# charginator_v1.net
KiCad netlist of a schematic drawn in EAGLE
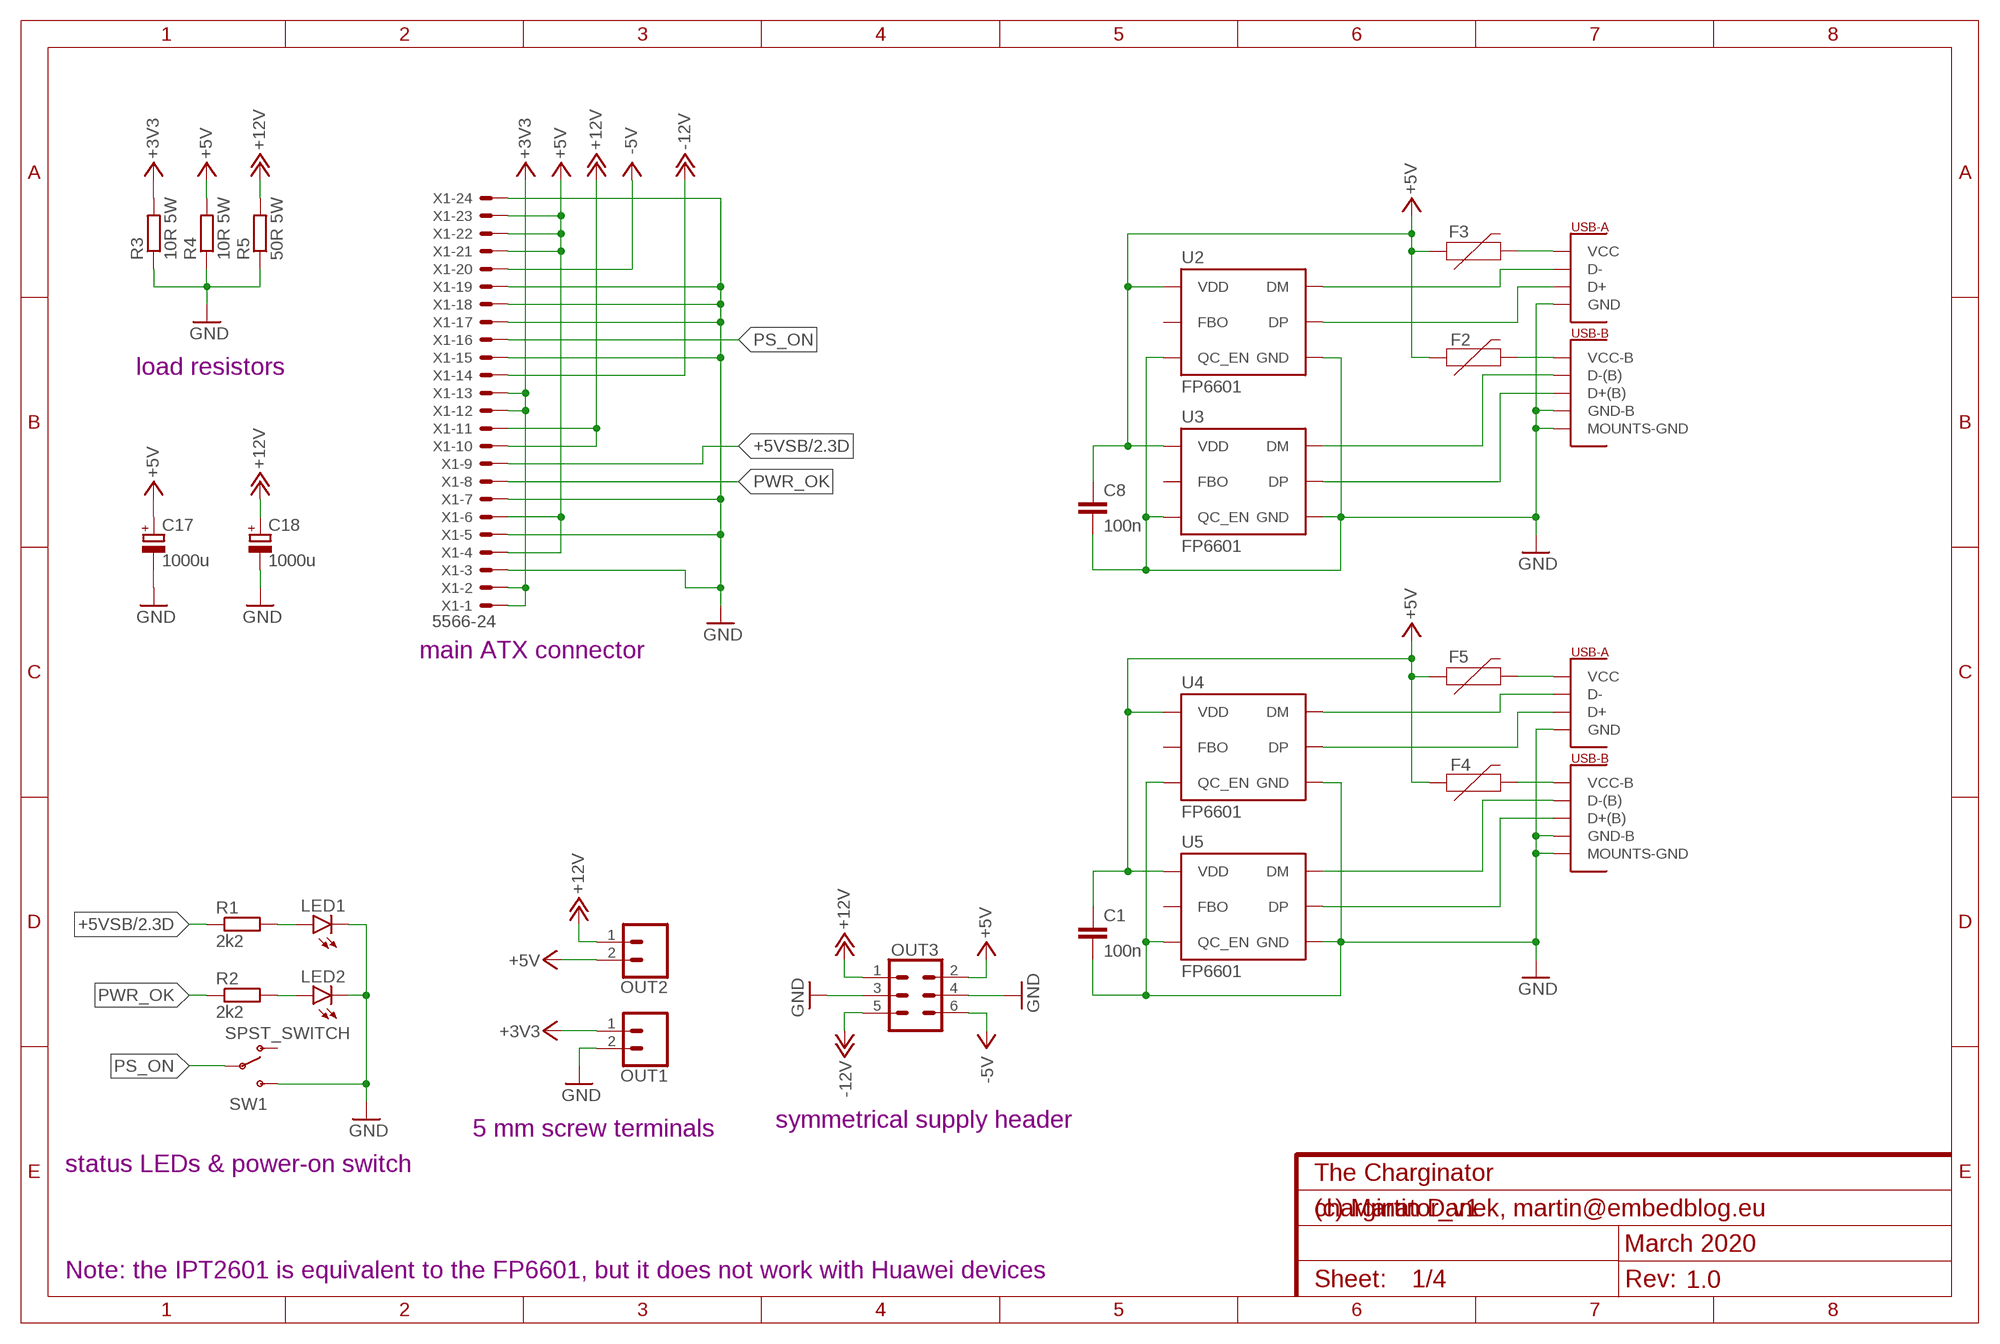
[diagram p0: schematic, sheet 1]
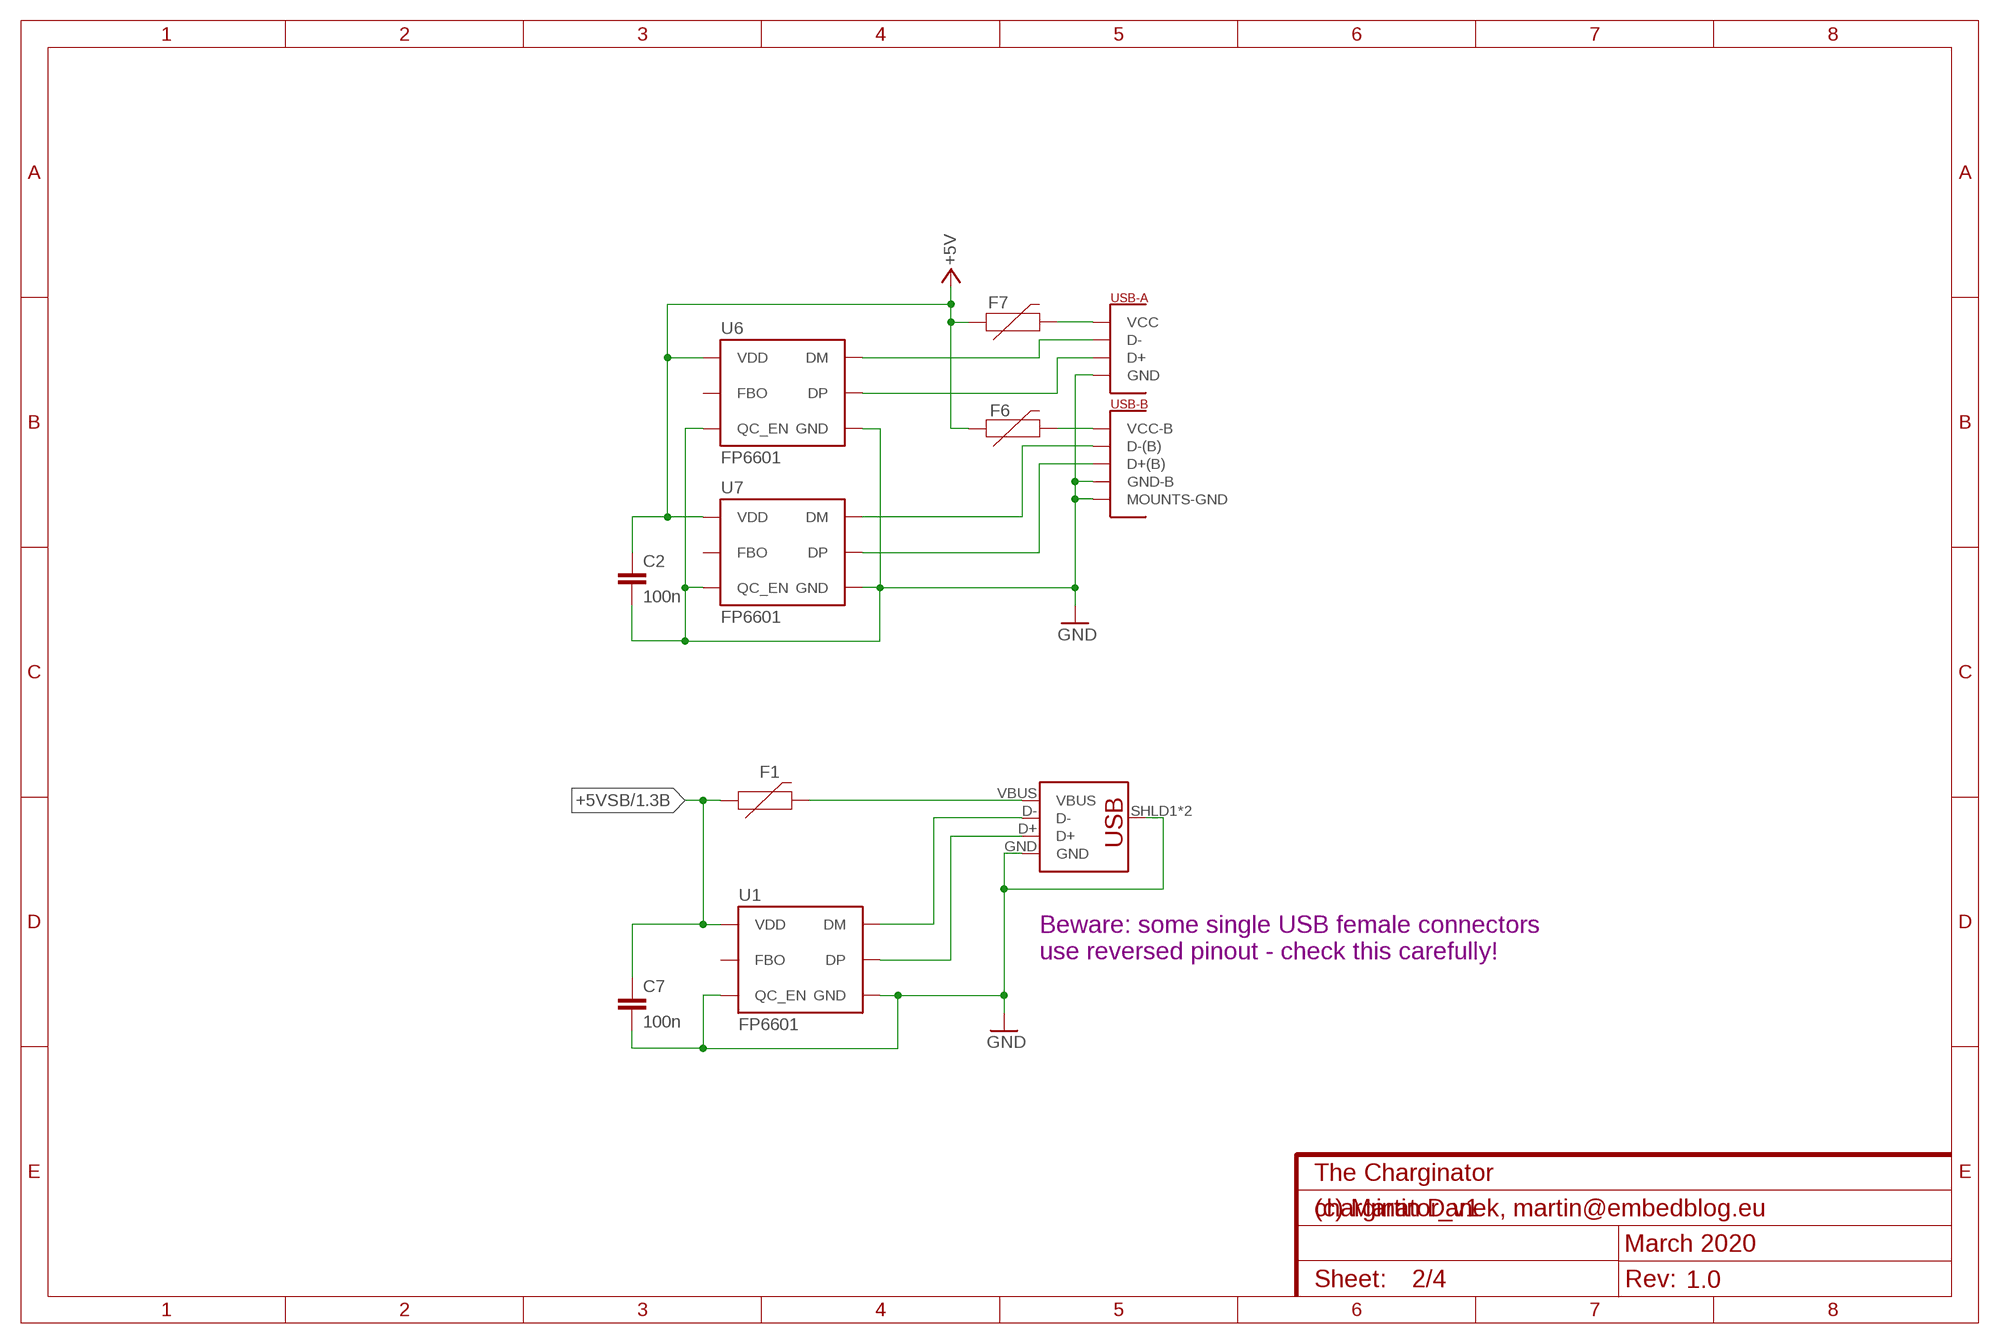
[diagram p1: schematic, sheet 2]
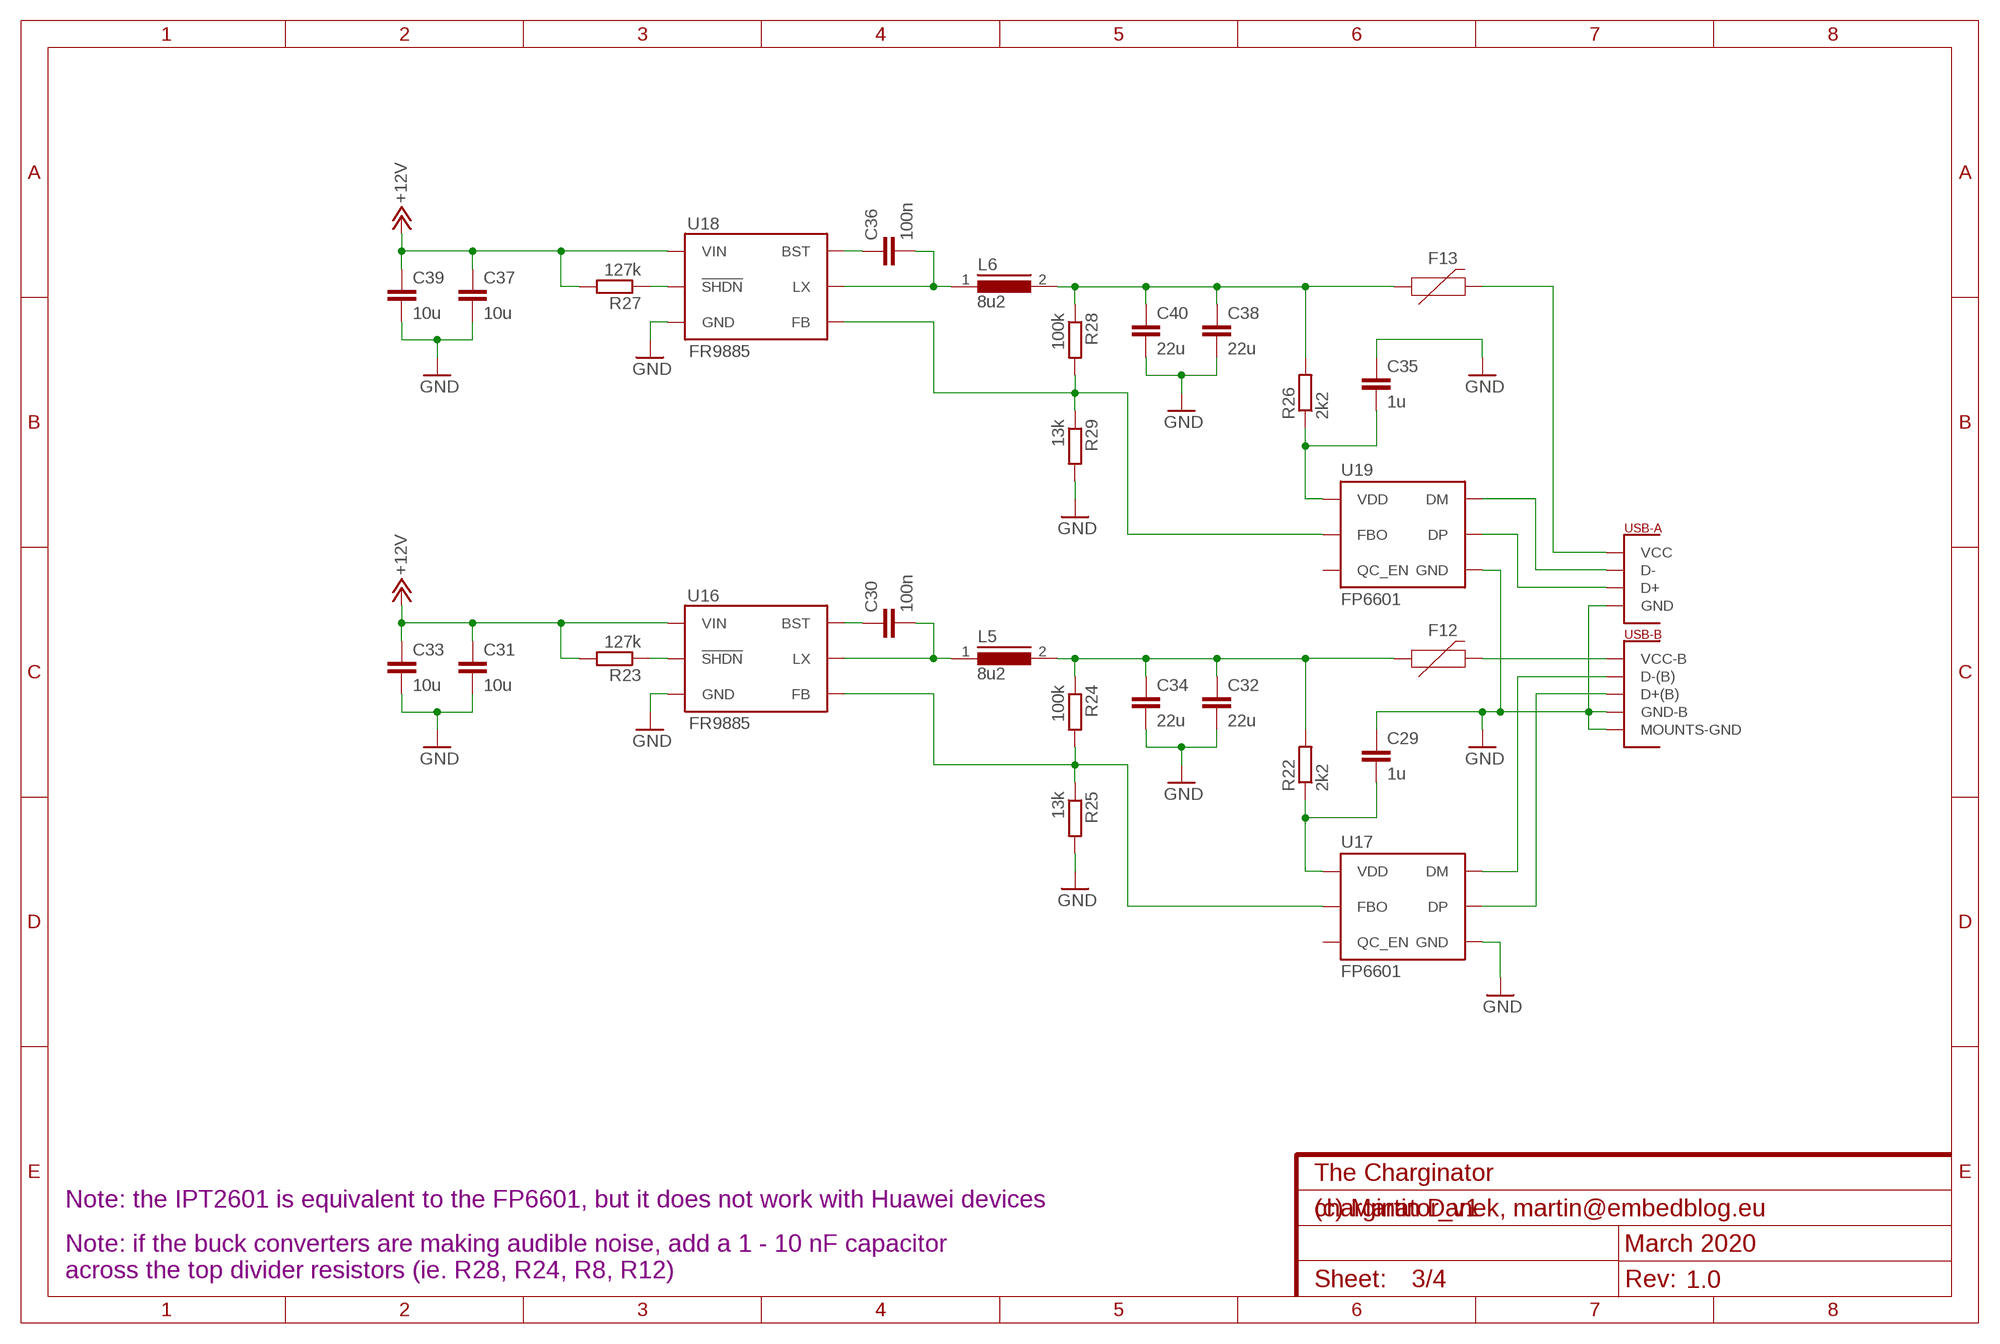
[diagram p2: schematic, sheet 3]
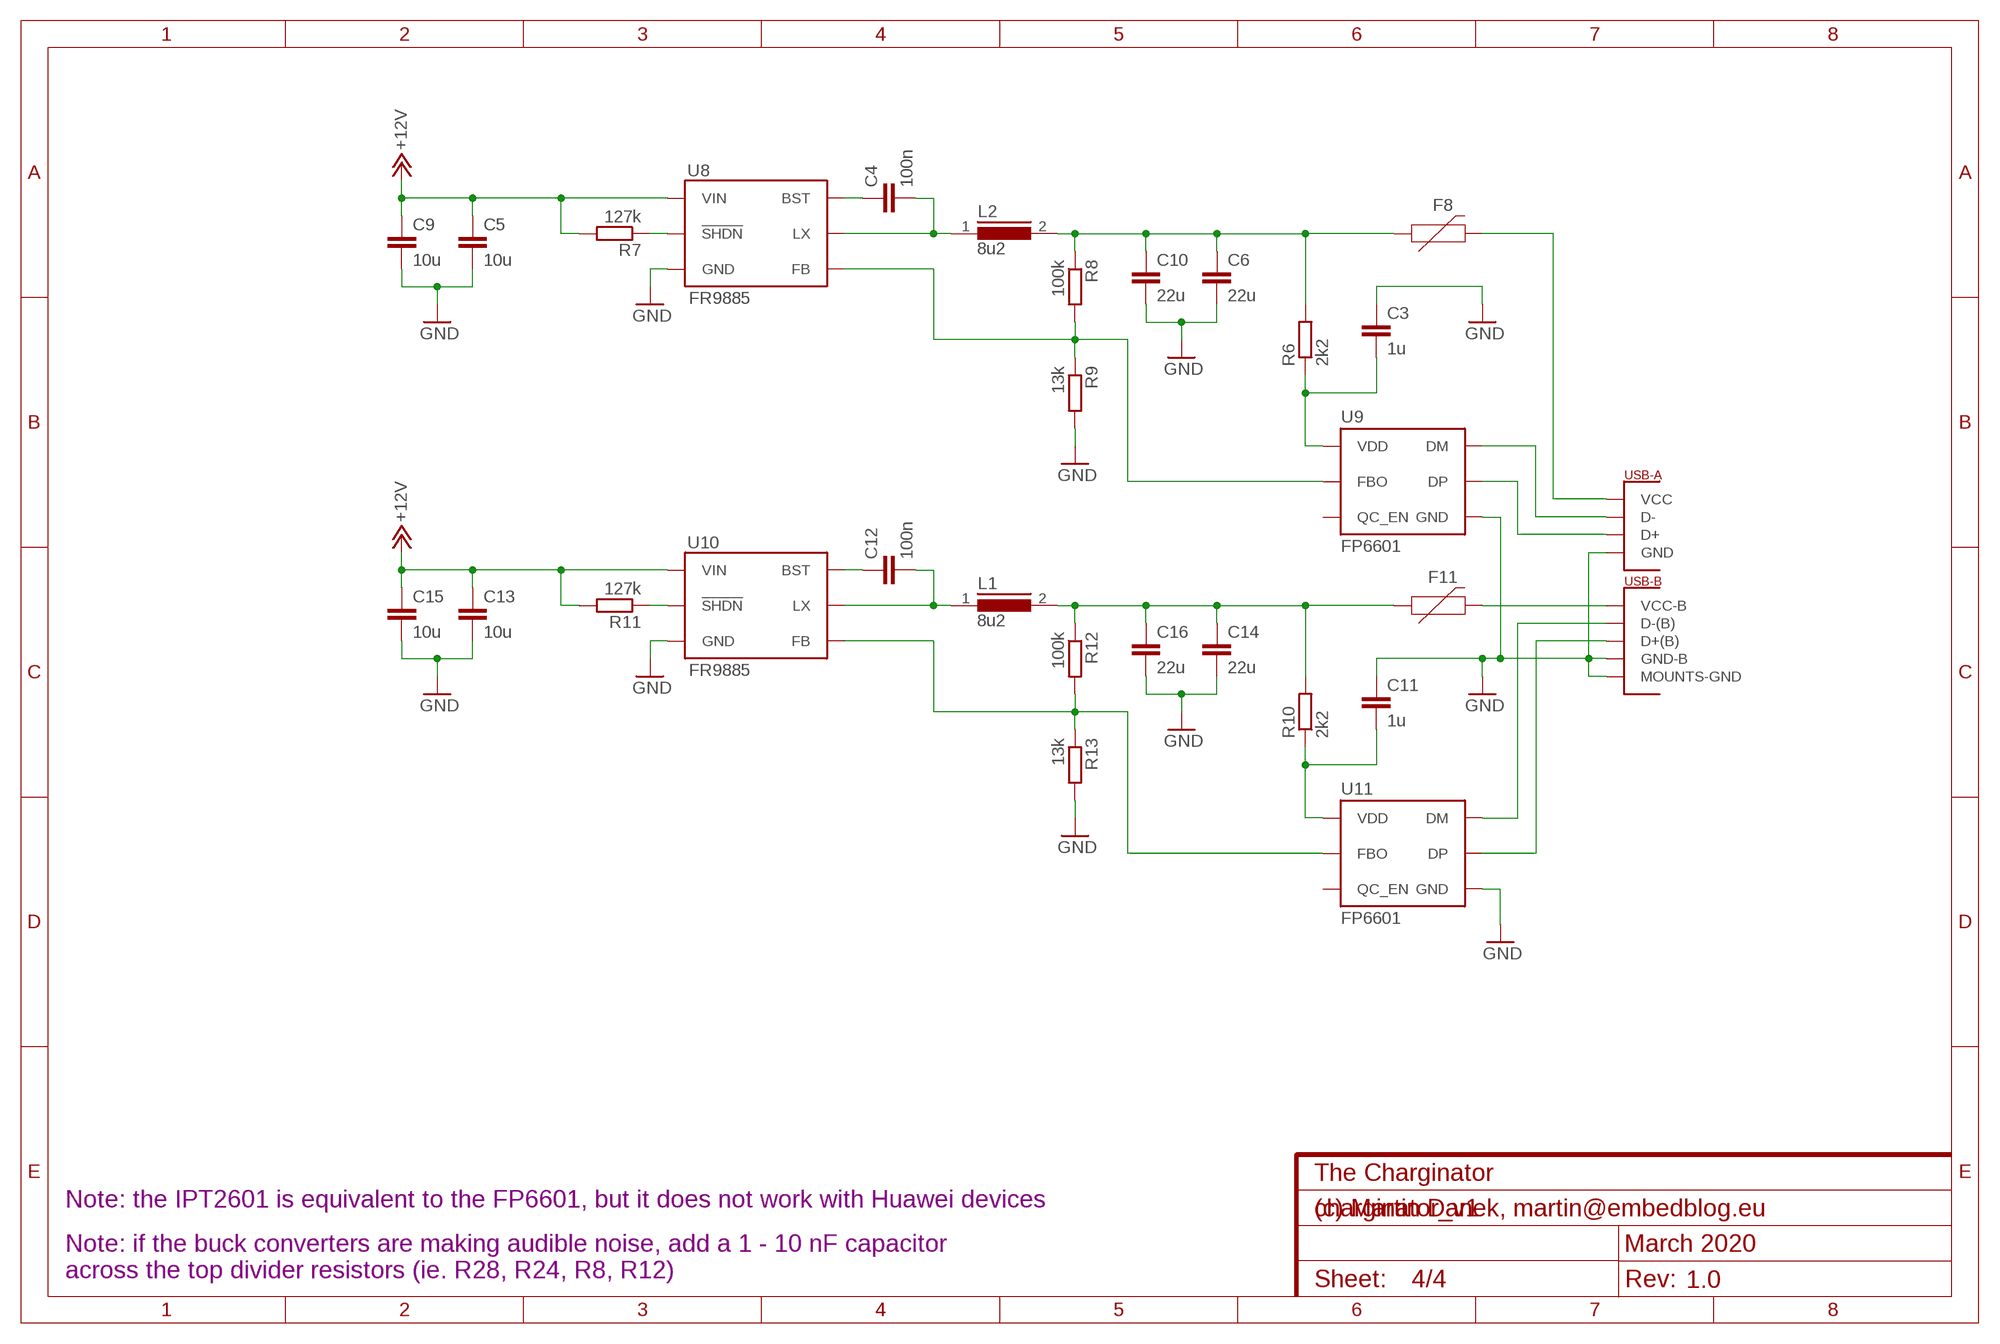
[diagram p3: schematic, sheet 4]

(export (version "E")
  (design (tool "Eeschema 10.0.6"))
  (components
    (comp (ref "C1")
      (value "100n")
      (footprint "eagle-import:C1206")
      (libsource (lib "eagle-import") (part "C-EUC1206"))
    )
    (comp (ref "C8")
      (value "100n")
      (footprint "eagle-import:C1206")
      (libsource (lib "eagle-import") (part "C-EUC1206"))
    )
    (comp (ref "C17")
      (value "1000u")
      (footprint "eagle-import:E5-10,5")
      (libsource (lib "eagle-import") (part "CPOL-EUE5-10.5"))
    )
    (comp (ref "C18")
      (value "1000u")
      (footprint "eagle-import:E5-13")
      (libsource (lib "eagle-import") (part "CPOL-EUE5-13"))
    )
    (comp (ref "F2")
      (value "6V/2A")
      (footprint "eagle-import:1206")
      (libsource (lib "eagle-import") (part "PPTC_HALF-AMP"))
    )
    (comp (ref "F3")
      (value "6V/2A")
      (footprint "eagle-import:1206")
      (libsource (lib "eagle-import") (part "PPTC_HALF-AMP"))
    )
    (comp (ref "F4")
      (value "6V/2A")
      (footprint "eagle-import:1206")
      (libsource (lib "eagle-import") (part "PPTC_HALF-AMP"))
    )
    (comp (ref "F5")
      (value "6V/2A")
      (footprint "eagle-import:1206")
      (libsource (lib "eagle-import") (part "PPTC_HALF-AMP"))
    )
    (comp (ref "LED1")
      (value "LED5MM")
      (footprint "eagle-import:LED5MM")
      (libsource (lib "eagle-import") (part "LED5MM"))
    )
    (comp (ref "LED2")
      (value "LED5MM")
      (footprint "eagle-import:LED5MM")
      (libsource (lib "eagle-import") (part "LED5MM"))
    )
    (comp (ref "OUT1")
      (value "5MM_SCREWTERMINAL_LARGE")
      (footprint "eagle-import:SCREWTERMINAL-5MM-2")
      (libsource (lib "eagle-import") (part "5MM_SCREWTERMINAL_LARGE"))
    )
    (comp (ref "OUT2")
      (value "5MM_SCREWTERMINAL_LARGE")
      (footprint "eagle-import:SCREWTERMINAL-5MM-2")
      (libsource (lib "eagle-import") (part "5MM_SCREWTERMINAL_LARGE"))
    )
    (comp (ref "OUT3")
      (value "FEMALE 2x3")
      (footprint "eagle-import:2X3")
      (libsource (lib "eagle-import") (part "CONN_03X2FEMALE"))
    )
    (comp (ref "R1")
      (value "2k2")
      (footprint "eagle-import:M1206")
      (libsource (lib "eagle-import") (part "R-EU_M1206"))
    )
    (comp (ref "R2")
      (value "2k2")
      (footprint "eagle-import:M1206")
      (libsource (lib "eagle-import") (part "R-EU_M1206"))
    )
    (comp (ref "R3")
      (value "10R 5W")
      (footprint "eagle-import:POWER_RESISTOR_5W")
      (libsource (lib "eagle-import") (part "RESISTOR_5W"))
    )
    (comp (ref "R4")
      (value "10R 5W")
      (footprint "eagle-import:POWER_RESISTOR_5W")
      (libsource (lib "eagle-import") (part "RESISTOR_5W"))
    )
    (comp (ref "R5")
      (value "50R 5W")
      (footprint "eagle-import:POWER_RESISTOR_5W")
      (libsource (lib "eagle-import") (part "RESISTOR_5W"))
    )
    (comp (ref "SW1")
      (value "SPST_SWITCH")
      (footprint "eagle-import:TL3XYO")
      (libsource (lib "eagle-import") (part "SPST_SWITCH"))
    )
    (comp (ref "U$1")
      (value "DUAL-PORT-USB-REC")
      (footprint "eagle-import:DUAL-PORT-USB")
      (libsource (lib "eagle-import") (part "DUAL-PORT-USB-REC"))
    )
    (comp (ref "U$2")
      (value "DUAL-PORT-USB-REC")
      (footprint "eagle-import:DUAL-PORT-USB")
      (libsource (lib "eagle-import") (part "DUAL-PORT-USB-REC"))
    )
    (comp (ref "U2")
      (value "FP6601")
      (footprint "eagle-import:SOT23-6")
      (libsource (lib "eagle-import") (part "IPT2601"))
    )
    (comp (ref "U3")
      (value "FP6601")
      (footprint "eagle-import:SOT23-6")
      (libsource (lib "eagle-import") (part "IPT2601"))
    )
    (comp (ref "U4")
      (value "FP6601")
      (footprint "eagle-import:SOT23-6")
      (libsource (lib "eagle-import") (part "IPT2601"))
    )
    (comp (ref "U5")
      (value "FP6601")
      (footprint "eagle-import:SOT23-6")
      (libsource (lib "eagle-import") (part "IPT2601"))
    )
    (comp (ref "X1")
      (value "5566-24")
      (footprint "eagle-import:5566-24")
      (fields (field (name "MF") "MOLEX"))
      (libsource (lib "eagle-import") (part "5566-24"))
    )
    (comp (ref "C2")
      (value "100n")
      (footprint "eagle-import:C1206")
      (libsource (lib "eagle-import") (part "C-EUC1206"))
    )
    (comp (ref "C7")
      (value "100n")
      (footprint "eagle-import:C1206")
      (libsource (lib "eagle-import") (part "C-EUC1206"))
    )
    (comp (ref "F1")
      (value "6V/2A")
      (footprint "eagle-import:1206")
      (libsource (lib "eagle-import") (part "PPTC_HALF-AMP"))
    )
    (comp (ref "F6")
      (value "6V/2A")
      (footprint "eagle-import:1206")
      (libsource (lib "eagle-import") (part "PPTC_HALF-AMP"))
    )
    (comp (ref "F7")
      (value "6V/2A")
      (footprint "eagle-import:1206")
      (libsource (lib "eagle-import") (part "PPTC_HALF-AMP"))
    )
    (comp (ref "U$3")
      (value "DUAL-PORT-USB-REC")
      (footprint "eagle-import:DUAL-PORT-USB")
      (libsource (lib "eagle-import") (part "DUAL-PORT-USB-REC"))
    )
    (comp (ref "U$5")
      (value "USB_A_REVERSED")
      (footprint "eagle-import:USB-A-S-SILK-FEMALE")
      (libsource (lib "eagle-import") (part "USB_A_REVERSED"))
    )
    (comp (ref "U1")
      (value "FP6601")
      (footprint "eagle-import:SOT23-6")
      (libsource (lib "eagle-import") (part "IPT2601"))
    )
    (comp (ref "U6")
      (value "FP6601")
      (footprint "eagle-import:SOT23-6")
      (libsource (lib "eagle-import") (part "IPT2601"))
    )
    (comp (ref "U7")
      (value "FP6601")
      (footprint "eagle-import:SOT23-6")
      (libsource (lib "eagle-import") (part "IPT2601"))
    )
    (comp (ref "C29")
      (value "1u")
      (footprint "eagle-import:C1206")
      (libsource (lib "eagle-import") (part "C-EUC1206"))
    )
    (comp (ref "C30")
      (value "100n")
      (footprint "eagle-import:C1206")
      (libsource (lib "eagle-import") (part "C-EUC1206"))
    )
    (comp (ref "C31")
      (value "10u")
      (footprint "eagle-import:C1206")
      (libsource (lib "eagle-import") (part "C-EUC1206"))
    )
    (comp (ref "C32")
      (value "22u")
      (footprint "eagle-import:C1206")
      (libsource (lib "eagle-import") (part "C-EUC1206"))
    )
    (comp (ref "C33")
      (value "10u")
      (footprint "eagle-import:C1206")
      (libsource (lib "eagle-import") (part "C-EUC1206"))
    )
    (comp (ref "C34")
      (value "22u")
      (footprint "eagle-import:C1206")
      (libsource (lib "eagle-import") (part "C-EUC1206"))
    )
    (comp (ref "C35")
      (value "1u")
      (footprint "eagle-import:C1206")
      (libsource (lib "eagle-import") (part "C-EUC1206"))
    )
    (comp (ref "C36")
      (value "100n")
      (footprint "eagle-import:C1206")
      (libsource (lib "eagle-import") (part "C-EUC1206"))
    )
    (comp (ref "C37")
      (value "10u")
      (footprint "eagle-import:C1206")
      (libsource (lib "eagle-import") (part "C-EUC1206"))
    )
    (comp (ref "C38")
      (value "22u")
      (footprint "eagle-import:C1206")
      (libsource (lib "eagle-import") (part "C-EUC1206"))
    )
    (comp (ref "C39")
      (value "10u")
      (footprint "eagle-import:C1206")
      (libsource (lib "eagle-import") (part "C-EUC1206"))
    )
    (comp (ref "C40")
      (value "22u")
      (footprint "eagle-import:C1206")
      (libsource (lib "eagle-import") (part "C-EUC1206"))
    )
    (comp (ref "F12")
      (value "12V/2A")
      (footprint "eagle-import:1206")
      (libsource (lib "eagle-import") (part "PPTC_HALF-AMP"))
    )
    (comp (ref "F13")
      (value "12V/2A")
      (footprint "eagle-import:1206")
      (libsource (lib "eagle-import") (part "PPTC_HALF-AMP"))
    )
    (comp (ref "L5")
      (value "8u2")
      (footprint "eagle-import:DR73")
      (libsource (lib "eagle-import") (part "DR73"))
    )
    (comp (ref "L6")
      (value "8u2")
      (footprint "eagle-import:DR73")
      (libsource (lib "eagle-import") (part "DR73"))
    )
    (comp (ref "R22")
      (value "2k2")
      (footprint "eagle-import:R1206")
      (libsource (lib "eagle-import") (part "R-EU_R1206"))
    )
    (comp (ref "R23")
      (value "127k")
      (footprint "eagle-import:R1206")
      (libsource (lib "eagle-import") (part "R-EU_R1206"))
    )
    (comp (ref "R24")
      (value "100k")
      (footprint "eagle-import:R1206")
      (libsource (lib "eagle-import") (part "R-EU_R1206"))
    )
    (comp (ref "R25")
      (value "13k")
      (footprint "eagle-import:R1206")
      (libsource (lib "eagle-import") (part "R-EU_R1206"))
    )
    (comp (ref "R26")
      (value "2k2")
      (footprint "eagle-import:R1206")
      (libsource (lib "eagle-import") (part "R-EU_R1206"))
    )
    (comp (ref "R27")
      (value "127k")
      (footprint "eagle-import:R1206")
      (libsource (lib "eagle-import") (part "R-EU_R1206"))
    )
    (comp (ref "R28")
      (value "100k")
      (footprint "eagle-import:R1206")
      (libsource (lib "eagle-import") (part "R-EU_R1206"))
    )
    (comp (ref "R29")
      (value "13k")
      (footprint "eagle-import:R1206")
      (libsource (lib "eagle-import") (part "R-EU_R1206"))
    )
    (comp (ref "U$6")
      (value "DUAL-PORT-USB-REC")
      (footprint "eagle-import:DUAL-PORT-USB")
      (libsource (lib "eagle-import") (part "DUAL-PORT-USB-REC"))
    )
    (comp (ref "U16")
      (value "FR9885")
      (footprint "eagle-import:SOT23-6")
      (libsource (lib "eagle-import") (part "FR9885"))
    )
    (comp (ref "U17")
      (value "FP6601")
      (footprint "eagle-import:SOT23-6")
      (libsource (lib "eagle-import") (part "IPT2601"))
    )
    (comp (ref "U18")
      (value "FR9885")
      (footprint "eagle-import:SOT23-6")
      (libsource (lib "eagle-import") (part "FR9885"))
    )
    (comp (ref "U19")
      (value "FP6601")
      (footprint "eagle-import:SOT23-6")
      (libsource (lib "eagle-import") (part "IPT2601"))
    )
    (comp (ref "C3")
      (value "1u")
      (footprint "eagle-import:C1206")
      (libsource (lib "eagle-import") (part "C-EUC1206"))
    )
    (comp (ref "C4")
      (value "100n")
      (footprint "eagle-import:C1206")
      (libsource (lib "eagle-import") (part "C-EUC1206"))
    )
    (comp (ref "C5")
      (value "10u")
      (footprint "eagle-import:C1206")
      (libsource (lib "eagle-import") (part "C-EUC1206"))
    )
    (comp (ref "C6")
      (value "22u")
      (footprint "eagle-import:C1206")
      (libsource (lib "eagle-import") (part "C-EUC1206"))
    )
    (comp (ref "C9")
      (value "10u")
      (footprint "eagle-import:C1206")
      (libsource (lib "eagle-import") (part "C-EUC1206"))
    )
    (comp (ref "C10")
      (value "22u")
      (footprint "eagle-import:C1206")
      (libsource (lib "eagle-import") (part "C-EUC1206"))
    )
    (comp (ref "C11")
      (value "1u")
      (footprint "eagle-import:C1206")
      (libsource (lib "eagle-import") (part "C-EUC1206"))
    )
    (comp (ref "C12")
      (value "100n")
      (footprint "eagle-import:C1206")
      (libsource (lib "eagle-import") (part "C-EUC1206"))
    )
    (comp (ref "C13")
      (value "10u")
      (footprint "eagle-import:C1206")
      (libsource (lib "eagle-import") (part "C-EUC1206"))
    )
    (comp (ref "C14")
      (value "22u")
      (footprint "eagle-import:C1206")
      (libsource (lib "eagle-import") (part "C-EUC1206"))
    )
    (comp (ref "C15")
      (value "10u")
      (footprint "eagle-import:C1206")
      (libsource (lib "eagle-import") (part "C-EUC1206"))
    )
    (comp (ref "C16")
      (value "22u")
      (footprint "eagle-import:C1206")
      (libsource (lib "eagle-import") (part "C-EUC1206"))
    )
    (comp (ref "F8")
      (value "12V/2A")
      (footprint "eagle-import:1206")
      (libsource (lib "eagle-import") (part "PPTC_HALF-AMP"))
    )
    (comp (ref "F11")
      (value "12V/2A")
      (footprint "eagle-import:1206")
      (libsource (lib "eagle-import") (part "PPTC_HALF-AMP"))
    )
    (comp (ref "L1")
      (value "8u2")
      (footprint "eagle-import:DR73")
      (libsource (lib "eagle-import") (part "DR73"))
    )
    (comp (ref "L2")
      (value "8u2")
      (footprint "eagle-import:DR73")
      (libsource (lib "eagle-import") (part "DR73"))
    )
    (comp (ref "R6")
      (value "2k2")
      (footprint "eagle-import:R1206")
      (libsource (lib "eagle-import") (part "R-EU_R1206"))
    )
    (comp (ref "R7")
      (value "127k")
      (footprint "eagle-import:R1206")
      (libsource (lib "eagle-import") (part "R-EU_R1206"))
    )
    (comp (ref "R8")
      (value "100k")
      (footprint "eagle-import:R1206")
      (libsource (lib "eagle-import") (part "R-EU_R1206"))
    )
    (comp (ref "R9")
      (value "13k")
      (footprint "eagle-import:R1206")
      (libsource (lib "eagle-import") (part "R-EU_R1206"))
    )
    (comp (ref "R10")
      (value "2k2")
      (footprint "eagle-import:R1206")
      (libsource (lib "eagle-import") (part "R-EU_R1206"))
    )
    (comp (ref "R11")
      (value "127k")
      (footprint "eagle-import:R1206")
      (libsource (lib "eagle-import") (part "R-EU_R1206"))
    )
    (comp (ref "R12")
      (value "100k")
      (footprint "eagle-import:R1206")
      (libsource (lib "eagle-import") (part "R-EU_R1206"))
    )
    (comp (ref "R13")
      (value "13k")
      (footprint "eagle-import:R1206")
      (libsource (lib "eagle-import") (part "R-EU_R1206"))
    )
    (comp (ref "U$4")
      (value "DUAL-PORT-USB-REC")
      (footprint "eagle-import:DUAL-PORT-USB")
      (libsource (lib "eagle-import") (part "DUAL-PORT-USB-REC"))
    )
    (comp (ref "U8")
      (value "FR9885")
      (footprint "eagle-import:SOT23-6")
      (libsource (lib "eagle-import") (part "FR9885"))
    )
    (comp (ref "U9")
      (value "FP6601")
      (footprint "eagle-import:SOT23-6")
      (libsource (lib "eagle-import") (part "IPT2601"))
    )
    (comp (ref "U10")
      (value "FR9885")
      (footprint "eagle-import:SOT23-6")
      (libsource (lib "eagle-import") (part "FR9885"))
    )
    (comp (ref "U11")
      (value "FP6601")
      (footprint "eagle-import:SOT23-6")
      (libsource (lib "eagle-import") (part "IPT2601"))
    )
  )
  (nets
    (net (code "1") (name "+3V3") (class "Default")
      (node (ref "OUT1") (pin "1") (pinfunction "1_1") (pintype "passive"))
      (node (ref "R3") (pin "P$2") (pinfunction "2_P$2") (pintype "passive"))
      (node (ref "X1") (pin "1") (pinfunction "S_1") (pintype "passive"))
      (node (ref "X1") (pin "12") (pinfunction "S_12") (pintype "passive"))
      (node (ref "X1") (pin "13") (pinfunction "S_13") (pintype "passive"))
      (node (ref "X1") (pin "2") (pinfunction "S_2") (pintype "passive"))
    )
    (net (code "2") (name "+5V") (class "Default")
      (node (ref "C1") (pin "1") (pinfunction "1_1") (pintype "passive"))
      (node (ref "C17") (pin "+") (pinfunction "+_+") (pintype "passive"))
      (node (ref "C2") (pin "1") (pinfunction "1_1") (pintype "passive"))
      (node (ref "C8") (pin "1") (pinfunction "1_1") (pintype "passive"))
      (node (ref "F2") (pin "1") (pinfunction "1_1") (pintype "bidirectional"))
      (node (ref "F3") (pin "1") (pinfunction "1_1") (pintype "bidirectional"))
      (node (ref "F4") (pin "1") (pinfunction "1_1") (pintype "bidirectional"))
      (node (ref "F5") (pin "1") (pinfunction "1_1") (pintype "bidirectional"))
      (node (ref "F6") (pin "1") (pinfunction "1_1") (pintype "bidirectional"))
      (node (ref "F7") (pin "1") (pinfunction "1_1") (pintype "bidirectional"))
      (node (ref "OUT2") (pin "2") (pinfunction "2_2") (pintype "passive"))
      (node (ref "OUT3") (pin "2") (pinfunction "2_2") (pintype "bidirectional"))
      (node (ref "R4") (pin "P$2") (pinfunction "2_P$2") (pintype "passive"))
      (node (ref "U2") (pin "5") (pinfunction "VDD_5") (pintype "bidirectional"))
      (node (ref "U3") (pin "5") (pinfunction "VDD_5") (pintype "bidirectional"))
      (node (ref "U4") (pin "5") (pinfunction "VDD_5") (pintype "bidirectional"))
      (node (ref "U5") (pin "5") (pinfunction "VDD_5") (pintype "bidirectional"))
      (node (ref "U6") (pin "5") (pinfunction "VDD_5") (pintype "bidirectional"))
      (node (ref "U7") (pin "5") (pinfunction "VDD_5") (pintype "bidirectional"))
      (node (ref "X1") (pin "21") (pinfunction "S_21") (pintype "passive"))
      (node (ref "X1") (pin "22") (pinfunction "S_22") (pintype "passive"))
      (node (ref "X1") (pin "23") (pinfunction "S_23") (pintype "passive"))
      (node (ref "X1") (pin "4") (pinfunction "S_4") (pintype "passive"))
      (node (ref "X1") (pin "6") (pinfunction "S_6") (pintype "passive"))
    )
    (net (code "3") (name "+5VSB") (class "Default")
      (node (ref "C7") (pin "1") (pinfunction "1_1") (pintype "passive"))
      (node (ref "F1") (pin "1") (pinfunction "1_1") (pintype "bidirectional"))
      (node (ref "R1") (pin "1") (pinfunction "1_1") (pintype "passive"))
      (node (ref "U1") (pin "5") (pinfunction "VDD_5") (pintype "bidirectional"))
      (node (ref "X1") (pin "9") (pinfunction "S_9") (pintype "passive"))
    )
    (net (code "4") (name "+12V") (class "Default")
      (node (ref "C13") (pin "1") (pinfunction "1_1") (pintype "passive"))
      (node (ref "C15") (pin "1") (pinfunction "1_1") (pintype "passive"))
      (node (ref "C18") (pin "+") (pinfunction "+_+") (pintype "passive"))
      (node (ref "C31") (pin "1") (pinfunction "1_1") (pintype "passive"))
      (node (ref "C33") (pin "1") (pinfunction "1_1") (pintype "passive"))
      (node (ref "C37") (pin "1") (pinfunction "1_1") (pintype "passive"))
      (node (ref "C39") (pin "1") (pinfunction "1_1") (pintype "passive"))
      (node (ref "C5") (pin "1") (pinfunction "1_1") (pintype "passive"))
      (node (ref "C9") (pin "1") (pinfunction "1_1") (pintype "passive"))
      (node (ref "OUT2") (pin "1") (pinfunction "1_1") (pintype "passive"))
      (node (ref "OUT3") (pin "1") (pinfunction "1_1") (pintype "bidirectional"))
      (node (ref "R11") (pin "2") (pinfunction "2_2") (pintype "passive"))
      (node (ref "R23") (pin "2") (pinfunction "2_2") (pintype "passive"))
      (node (ref "R27") (pin "2") (pinfunction "2_2") (pintype "passive"))
      (node (ref "R5") (pin "P$2") (pinfunction "2_P$2") (pintype "passive"))
      (node (ref "R7") (pin "2") (pinfunction "2_2") (pintype "passive"))
      (node (ref "U10") (pin "5") (pinfunction "VIN_5") (pintype "bidirectional"))
      (node (ref "U16") (pin "5") (pinfunction "VIN_5") (pintype "bidirectional"))
      (node (ref "U18") (pin "5") (pinfunction "VIN_5") (pintype "bidirectional"))
      (node (ref "U8") (pin "5") (pinfunction "VIN_5") (pintype "bidirectional"))
      (node (ref "X1") (pin "10") (pinfunction "S_10") (pintype "passive"))
      (node (ref "X1") (pin "11") (pinfunction "S_11") (pintype "passive"))
    )
    (net (code "5") (name "-5V") (class "Default")
      (node (ref "OUT3") (pin "6") (pinfunction "6_6") (pintype "bidirectional"))
      (node (ref "X1") (pin "20") (pinfunction "S_20") (pintype "passive"))
    )
    (net (code "6") (name "-12V") (class "Default")
      (node (ref "OUT3") (pin "5") (pinfunction "5_5") (pintype "bidirectional"))
      (node (ref "X1") (pin "14") (pinfunction "S_14") (pintype "passive"))
    )
    (net (code "7") (name "GND") (class "Default")
      (node (ref "C1") (pin "2") (pinfunction "2_2") (pintype "passive"))
      (node (ref "C10") (pin "2") (pinfunction "2_2") (pintype "passive"))
      (node (ref "C11") (pin "1") (pinfunction "1_1") (pintype "passive"))
      (node (ref "C13") (pin "2") (pinfunction "2_2") (pintype "passive"))
      (node (ref "C14") (pin "2") (pinfunction "2_2") (pintype "passive"))
      (node (ref "C15") (pin "2") (pinfunction "2_2") (pintype "passive"))
      (node (ref "C16") (pin "2") (pinfunction "2_2") (pintype "passive"))
      (node (ref "C17") (pin "-") (pinfunction "-_-") (pintype "passive"))
      (node (ref "C18") (pin "-") (pinfunction "-_-") (pintype "passive"))
      (node (ref "C2") (pin "2") (pinfunction "2_2") (pintype "passive"))
      (node (ref "C29") (pin "1") (pinfunction "1_1") (pintype "passive"))
      (node (ref "C3") (pin "1") (pinfunction "1_1") (pintype "passive"))
      (node (ref "C31") (pin "2") (pinfunction "2_2") (pintype "passive"))
      (node (ref "C32") (pin "2") (pinfunction "2_2") (pintype "passive"))
      (node (ref "C33") (pin "2") (pinfunction "2_2") (pintype "passive"))
      (node (ref "C34") (pin "2") (pinfunction "2_2") (pintype "passive"))
      (node (ref "C35") (pin "1") (pinfunction "1_1") (pintype "passive"))
      (node (ref "C37") (pin "2") (pinfunction "2_2") (pintype "passive"))
      (node (ref "C38") (pin "2") (pinfunction "2_2") (pintype "passive"))
      (node (ref "C39") (pin "2") (pinfunction "2_2") (pintype "passive"))
      (node (ref "C40") (pin "2") (pinfunction "2_2") (pintype "passive"))
      (node (ref "C5") (pin "2") (pinfunction "2_2") (pintype "passive"))
      (node (ref "C6") (pin "2") (pinfunction "2_2") (pintype "passive"))
      (node (ref "C7") (pin "2") (pinfunction "2_2") (pintype "passive"))
      (node (ref "C8") (pin "2") (pinfunction "2_2") (pintype "passive"))
      (node (ref "C9") (pin "2") (pinfunction "2_2") (pintype "passive"))
      (node (ref "LED1") (pin "K") (pinfunction "C_K") (pintype "passive"))
      (node (ref "LED2") (pin "K") (pinfunction "C_K") (pintype "passive"))
      (node (ref "OUT1") (pin "2") (pinfunction "2_2") (pintype "passive"))
      (node (ref "OUT3") (pin "3") (pinfunction "3_3") (pintype "bidirectional"))
      (node (ref "OUT3") (pin "4") (pinfunction "4_4") (pintype "bidirectional"))
      (node (ref "R13") (pin "2") (pinfunction "2_2") (pintype "passive"))
      (node (ref "R25") (pin "2") (pinfunction "2_2") (pintype "passive"))
      (node (ref "R29") (pin "2") (pinfunction "2_2") (pintype "passive"))
      (node (ref "R3") (pin "P$1") (pinfunction "1_P$1") (pintype "passive"))
      (node (ref "R4") (pin "P$1") (pinfunction "1_P$1") (pintype "passive"))
      (node (ref "R5") (pin "P$1") (pinfunction "1_P$1") (pintype "passive"))
      (node (ref "R9") (pin "2") (pinfunction "2_2") (pintype "passive"))
      (node (ref "SW1") (pin "1") (pinfunction "S_1") (pintype "passive"))
      (node (ref "U$1") (pin "GND") (pinfunction "MOUNTS-GND_GND") (pintype "power_in"))
      (node (ref "U$1") (pin "P$11") (pinfunction "GND_P$11") (pintype "power_in"))
      (node (ref "U$1") (pin "P$2") (pinfunction "MOUNTS-GND_P$2") (pintype "power_in"))
      (node (ref "U$1") (pin "P$3") (pinfunction "MOUNTS-GND_P$3") (pintype "power_in"))
      (node (ref "U$1") (pin "P$4") (pinfunction "MOUNTS-GND_P$4") (pintype "power_in"))
      (node (ref "U$1") (pin "P$9") (pinfunction "GND-B_P$9") (pintype "power_in"))
      (node (ref "U$2") (pin "GND") (pinfunction "MOUNTS-GND_GND") (pintype "power_in"))
      (node (ref "U$2") (pin "P$11") (pinfunction "GND_P$11") (pintype "power_in"))
      (node (ref "U$2") (pin "P$2") (pinfunction "MOUNTS-GND_P$2") (pintype "power_in"))
      (node (ref "U$2") (pin "P$3") (pinfunction "MOUNTS-GND_P$3") (pintype "power_in"))
      (node (ref "U$2") (pin "P$4") (pinfunction "MOUNTS-GND_P$4") (pintype "power_in"))
      (node (ref "U$2") (pin "P$9") (pinfunction "GND-B_P$9") (pintype "power_in"))
      (node (ref "U$3") (pin "GND") (pinfunction "MOUNTS-GND_GND") (pintype "power_in"))
      (node (ref "U$3") (pin "P$11") (pinfunction "GND_P$11") (pintype "power_in"))
      (node (ref "U$3") (pin "P$2") (pinfunction "MOUNTS-GND_P$2") (pintype "power_in"))
      (node (ref "U$3") (pin "P$3") (pinfunction "MOUNTS-GND_P$3") (pintype "power_in"))
      (node (ref "U$3") (pin "P$4") (pinfunction "MOUNTS-GND_P$4") (pintype "power_in"))
      (node (ref "U$3") (pin "P$9") (pinfunction "GND-B_P$9") (pintype "power_in"))
      (node (ref "U$4") (pin "GND") (pinfunction "MOUNTS-GND_GND") (pintype "power_in"))
      (node (ref "U$4") (pin "P$11") (pinfunction "GND_P$11") (pintype "power_in"))
      (node (ref "U$4") (pin "P$2") (pinfunction "MOUNTS-GND_P$2") (pintype "power_in"))
      (node (ref "U$4") (pin "P$3") (pinfunction "MOUNTS-GND_P$3") (pintype "power_in"))
      (node (ref "U$4") (pin "P$4") (pinfunction "MOUNTS-GND_P$4") (pintype "power_in"))
      (node (ref "U$4") (pin "P$9") (pinfunction "GND-B_P$9") (pintype "power_in"))
      (node (ref "U$5") (pin "GND") (pinfunction "GND_GND") (pintype "power_in"))
      (node (ref "U$5") (pin "SHLD1") (pinfunction "SHIELD_SHLD1") (pintype "bidirectional"))
      (node (ref "U$5") (pin "SHLD2") (pinfunction "SHIELD_SHLD2") (pintype "bidirectional"))
      (node (ref "U$6") (pin "GND") (pinfunction "MOUNTS-GND_GND") (pintype "power_in"))
      (node (ref "U$6") (pin "P$11") (pinfunction "GND_P$11") (pintype "power_in"))
      (node (ref "U$6") (pin "P$2") (pinfunction "MOUNTS-GND_P$2") (pintype "power_in"))
      (node (ref "U$6") (pin "P$3") (pinfunction "MOUNTS-GND_P$3") (pintype "power_in"))
      (node (ref "U$6") (pin "P$4") (pinfunction "MOUNTS-GND_P$4") (pintype "power_in"))
      (node (ref "U$6") (pin "P$9") (pinfunction "GND-B_P$9") (pintype "power_in"))
      (node (ref "U1") (pin "2") (pinfunction "GND_2") (pintype "bidirectional"))
      (node (ref "U1") (pin "4") (pinfunction "QC_EN_4") (pintype "bidirectional"))
      (node (ref "U10") (pin "2") (pinfunction "GND_2") (pintype "bidirectional"))
      (node (ref "U11") (pin "2") (pinfunction "GND_2") (pintype "bidirectional"))
      (node (ref "U16") (pin "2") (pinfunction "GND_2") (pintype "bidirectional"))
      (node (ref "U17") (pin "2") (pinfunction "GND_2") (pintype "bidirectional"))
      (node (ref "U18") (pin "2") (pinfunction "GND_2") (pintype "bidirectional"))
      (node (ref "U19") (pin "2") (pinfunction "GND_2") (pintype "bidirectional"))
      (node (ref "U2") (pin "2") (pinfunction "GND_2") (pintype "bidirectional"))
      (node (ref "U2") (pin "4") (pinfunction "QC_EN_4") (pintype "bidirectional"))
      (node (ref "U3") (pin "2") (pinfunction "GND_2") (pintype "bidirectional"))
      (node (ref "U3") (pin "4") (pinfunction "QC_EN_4") (pintype "bidirectional"))
      (node (ref "U4") (pin "2") (pinfunction "GND_2") (pintype "bidirectional"))
      (node (ref "U4") (pin "4") (pinfunction "QC_EN_4") (pintype "bidirectional"))
      (node (ref "U5") (pin "2") (pinfunction "GND_2") (pintype "bidirectional"))
      (node (ref "U5") (pin "4") (pinfunction "QC_EN_4") (pintype "bidirectional"))
      (node (ref "U6") (pin "2") (pinfunction "GND_2") (pintype "bidirectional"))
      (node (ref "U6") (pin "4") (pinfunction "QC_EN_4") (pintype "bidirectional"))
      (node (ref "U7") (pin "2") (pinfunction "GND_2") (pintype "bidirectional"))
      (node (ref "U7") (pin "4") (pinfunction "QC_EN_4") (pintype "bidirectional"))
      (node (ref "U8") (pin "2") (pinfunction "GND_2") (pintype "bidirectional"))
      (node (ref "U9") (pin "2") (pinfunction "GND_2") (pintype "bidirectional"))
      (node (ref "X1") (pin "15") (pinfunction "S_15") (pintype "passive"))
      (node (ref "X1") (pin "17") (pinfunction "S_17") (pintype "passive"))
      (node (ref "X1") (pin "18") (pinfunction "S_18") (pintype "passive"))
      (node (ref "X1") (pin "19") (pinfunction "S_19") (pintype "passive"))
      (node (ref "X1") (pin "24") (pinfunction "S_24") (pintype "passive"))
      (node (ref "X1") (pin "3") (pinfunction "S_3") (pintype "passive"))
      (node (ref "X1") (pin "5") (pinfunction "S_5") (pintype "passive"))
      (node (ref "X1") (pin "7") (pinfunction "S_7") (pintype "passive"))
    )
    (net (code "8") (name "Net-(C10-Pad1)") (class "Default")
      (node (ref "C10") (pin "1") (pinfunction "1_1") (pintype "passive"))
      (node (ref "C6") (pin "1") (pinfunction "1_1") (pintype "passive"))
      (node (ref "F8") (pin "1") (pinfunction "1_1") (pintype "bidirectional"))
      (node (ref "L2") (pin "2") (pinfunction "2_2") (pintype "passive"))
      (node (ref "R6") (pin "2") (pinfunction "2_2") (pintype "passive"))
      (node (ref "R8") (pin "1") (pinfunction "1_1") (pintype "passive"))
    )
    (net (code "9") (name "Net-(C14-Pad1)") (class "Default")
      (node (ref "C14") (pin "1") (pinfunction "1_1") (pintype "passive"))
      (node (ref "C16") (pin "1") (pinfunction "1_1") (pintype "passive"))
      (node (ref "F11") (pin "1") (pinfunction "1_1") (pintype "bidirectional"))
      (node (ref "L1") (pin "2") (pinfunction "2_2") (pintype "passive"))
      (node (ref "R10") (pin "2") (pinfunction "2_2") (pintype "passive"))
      (node (ref "R12") (pin "1") (pinfunction "1_1") (pintype "passive"))
    )
    (net (code "10") (name "Net-(C32-Pad1)") (class "Default")
      (node (ref "C32") (pin "1") (pinfunction "1_1") (pintype "passive"))
      (node (ref "C34") (pin "1") (pinfunction "1_1") (pintype "passive"))
      (node (ref "F12") (pin "1") (pinfunction "1_1") (pintype "bidirectional"))
      (node (ref "L5") (pin "2") (pinfunction "2_2") (pintype "passive"))
      (node (ref "R22") (pin "2") (pinfunction "2_2") (pintype "passive"))
      (node (ref "R24") (pin "1") (pinfunction "1_1") (pintype "passive"))
    )
    (net (code "11") (name "Net-(C38-Pad1)") (class "Default")
      (node (ref "C38") (pin "1") (pinfunction "1_1") (pintype "passive"))
      (node (ref "C40") (pin "1") (pinfunction "1_1") (pintype "passive"))
      (node (ref "F13") (pin "1") (pinfunction "1_1") (pintype "bidirectional"))
      (node (ref "L6") (pin "2") (pinfunction "2_2") (pintype "passive"))
      (node (ref "R26") (pin "2") (pinfunction "2_2") (pintype "passive"))
      (node (ref "R28") (pin "1") (pinfunction "1_1") (pintype "passive"))
    )
    (net (code "12") (name "Net-(F1-Pad2)") (class "Default")
      (node (ref "F1") (pin "2") (pinfunction "2_2") (pintype "bidirectional"))
      (node (ref "U$5") (pin "VBUS") (pinfunction "VBUS_VBUS") (pintype "power_in"))
    )
    (net (code "13") (name "Net-(LED1-PadA)") (class "Default")
      (node (ref "LED1") (pin "A") (pinfunction "A_A") (pintype "passive"))
      (node (ref "R1") (pin "2") (pinfunction "2_2") (pintype "passive"))
    )
    (net (code "14") (name "Net-(LED2-PadA)") (class "Default")
      (node (ref "LED2") (pin "A") (pinfunction "A_A") (pintype "passive"))
      (node (ref "R2") (pin "2") (pinfunction "2_2") (pintype "passive"))
    )
    (net (code "15") (name "Net-(U$1-D+(B))") (class "Default")
      (node (ref "U$1") (pin "P$6") (pinfunction "D+(B)_P$6") (pintype "bidirectional"))
      (node (ref "U3") (pin "1") (pinfunction "DP_1") (pintype "bidirectional"))
    )
    (net (code "16") (name "Net-(U$1-D+)") (class "Default")
      (node (ref "U$1") (pin "P$8") (pinfunction "D+_P$8") (pintype "bidirectional"))
      (node (ref "U2") (pin "1") (pinfunction "DP_1") (pintype "bidirectional"))
    )
    (net (code "17") (name "Net-(U$1-D-(B))") (class "Default")
      (node (ref "U$1") (pin "P$5") (pinfunction "D-(B)_P$5") (pintype "bidirectional"))
      (node (ref "U3") (pin "6") (pinfunction "DM_6") (pintype "bidirectional"))
    )
    (net (code "18") (name "Net-(U$1-D-)") (class "Default")
      (node (ref "U$1") (pin "P$7") (pinfunction "D-_P$7") (pintype "bidirectional"))
      (node (ref "U2") (pin "6") (pinfunction "DM_6") (pintype "bidirectional"))
    )
    (net (code "19") (name "Net-(U$1-VCC)") (class "Default")
      (node (ref "F3") (pin "2") (pinfunction "2_2") (pintype "bidirectional"))
      (node (ref "U$1") (pin "P$12") (pinfunction "VCC_P$12") (pintype "power_in"))
    )
    (net (code "20") (name "Net-(U$1-VCC-B)") (class "Default")
      (node (ref "F2") (pin "2") (pinfunction "2_2") (pintype "bidirectional"))
      (node (ref "U$1") (pin "P$10") (pinfunction "VCC-B_P$10") (pintype "power_in"))
    )
    (net (code "21") (name "Net-(U$2-D+(B))") (class "Default")
      (node (ref "U$2") (pin "P$6") (pinfunction "D+(B)_P$6") (pintype "bidirectional"))
      (node (ref "U5") (pin "1") (pinfunction "DP_1") (pintype "bidirectional"))
    )
    (net (code "22") (name "Net-(U$2-D+)") (class "Default")
      (node (ref "U$2") (pin "P$8") (pinfunction "D+_P$8") (pintype "bidirectional"))
      (node (ref "U4") (pin "1") (pinfunction "DP_1") (pintype "bidirectional"))
    )
    (net (code "23") (name "Net-(U$2-D-(B))") (class "Default")
      (node (ref "U$2") (pin "P$5") (pinfunction "D-(B)_P$5") (pintype "bidirectional"))
      (node (ref "U5") (pin "6") (pinfunction "DM_6") (pintype "bidirectional"))
    )
    (net (code "24") (name "Net-(U$2-D-)") (class "Default")
      (node (ref "U$2") (pin "P$7") (pinfunction "D-_P$7") (pintype "bidirectional"))
      (node (ref "U4") (pin "6") (pinfunction "DM_6") (pintype "bidirectional"))
    )
    (net (code "25") (name "Net-(U$2-VCC)") (class "Default")
      (node (ref "F5") (pin "2") (pinfunction "2_2") (pintype "bidirectional"))
      (node (ref "U$2") (pin "P$12") (pinfunction "VCC_P$12") (pintype "power_in"))
    )
    (net (code "26") (name "Net-(U$2-VCC-B)") (class "Default")
      (node (ref "F4") (pin "2") (pinfunction "2_2") (pintype "bidirectional"))
      (node (ref "U$2") (pin "P$10") (pinfunction "VCC-B_P$10") (pintype "power_in"))
    )
    (net (code "27") (name "Net-(U$3-D+(B))") (class "Default")
      (node (ref "U$3") (pin "P$6") (pinfunction "D+(B)_P$6") (pintype "bidirectional"))
      (node (ref "U7") (pin "1") (pinfunction "DP_1") (pintype "bidirectional"))
    )
    (net (code "28") (name "Net-(U$3-D+)") (class "Default")
      (node (ref "U$3") (pin "P$8") (pinfunction "D+_P$8") (pintype "bidirectional"))
      (node (ref "U6") (pin "1") (pinfunction "DP_1") (pintype "bidirectional"))
    )
    (net (code "29") (name "Net-(U$3-D-(B))") (class "Default")
      (node (ref "U$3") (pin "P$5") (pinfunction "D-(B)_P$5") (pintype "bidirectional"))
      (node (ref "U7") (pin "6") (pinfunction "DM_6") (pintype "bidirectional"))
    )
    (net (code "30") (name "Net-(U$3-D-)") (class "Default")
      (node (ref "U$3") (pin "P$7") (pinfunction "D-_P$7") (pintype "bidirectional"))
      (node (ref "U6") (pin "6") (pinfunction "DM_6") (pintype "bidirectional"))
    )
    (net (code "31") (name "Net-(U$3-VCC)") (class "Default")
      (node (ref "F7") (pin "2") (pinfunction "2_2") (pintype "bidirectional"))
      (node (ref "U$3") (pin "P$12") (pinfunction "VCC_P$12") (pintype "power_in"))
    )
    (net (code "32") (name "Net-(U$3-VCC-B)") (class "Default")
      (node (ref "F6") (pin "2") (pinfunction "2_2") (pintype "bidirectional"))
      (node (ref "U$3") (pin "P$10") (pinfunction "VCC-B_P$10") (pintype "power_in"))
    )
    (net (code "33") (name "Net-(U$4-D+(B))") (class "Default")
      (node (ref "U$4") (pin "P$6") (pinfunction "D+(B)_P$6") (pintype "bidirectional"))
      (node (ref "U11") (pin "1") (pinfunction "DP_1") (pintype "bidirectional"))
    )
    (net (code "34") (name "Net-(U$4-D+)") (class "Default")
      (node (ref "U$4") (pin "P$8") (pinfunction "D+_P$8") (pintype "bidirectional"))
      (node (ref "U9") (pin "1") (pinfunction "DP_1") (pintype "bidirectional"))
    )
    (net (code "35") (name "Net-(U$4-D-(B))") (class "Default")
      (node (ref "U$4") (pin "P$5") (pinfunction "D-(B)_P$5") (pintype "bidirectional"))
      (node (ref "U11") (pin "6") (pinfunction "DM_6") (pintype "bidirectional"))
    )
    (net (code "36") (name "Net-(U$4-D-)") (class "Default")
      (node (ref "U$4") (pin "P$7") (pinfunction "D-_P$7") (pintype "bidirectional"))
      (node (ref "U9") (pin "6") (pinfunction "DM_6") (pintype "bidirectional"))
    )
    (net (code "37") (name "Net-(U$4-VCC)") (class "Default")
      (node (ref "F8") (pin "2") (pinfunction "2_2") (pintype "bidirectional"))
      (node (ref "U$4") (pin "P$12") (pinfunction "VCC_P$12") (pintype "power_in"))
    )
    (net (code "38") (name "Net-(U$4-VCC-B)") (class "Default")
      (node (ref "F11") (pin "2") (pinfunction "2_2") (pintype "bidirectional"))
      (node (ref "U$4") (pin "P$10") (pinfunction "VCC-B_P$10") (pintype "power_in"))
    )
    (net (code "39") (name "Net-(U$6-D+(B))") (class "Default")
      (node (ref "U$6") (pin "P$6") (pinfunction "D+(B)_P$6") (pintype "bidirectional"))
      (node (ref "U17") (pin "1") (pinfunction "DP_1") (pintype "bidirectional"))
    )
    (net (code "40") (name "Net-(U$6-D+)") (class "Default")
      (node (ref "U$6") (pin "P$8") (pinfunction "D+_P$8") (pintype "bidirectional"))
      (node (ref "U19") (pin "1") (pinfunction "DP_1") (pintype "bidirectional"))
    )
    (net (code "41") (name "Net-(U$6-D-(B))") (class "Default")
      (node (ref "U$6") (pin "P$5") (pinfunction "D-(B)_P$5") (pintype "bidirectional"))
      (node (ref "U17") (pin "6") (pinfunction "DM_6") (pintype "bidirectional"))
    )
    (net (code "42") (name "Net-(U$6-D-)") (class "Default")
      (node (ref "U$6") (pin "P$7") (pinfunction "D-_P$7") (pintype "bidirectional"))
      (node (ref "U19") (pin "6") (pinfunction "DM_6") (pintype "bidirectional"))
    )
    (net (code "43") (name "Net-(U$6-VCC)") (class "Default")
      (node (ref "F13") (pin "2") (pinfunction "2_2") (pintype "bidirectional"))
      (node (ref "U$6") (pin "P$12") (pinfunction "VCC_P$12") (pintype "power_in"))
    )
    (net (code "44") (name "Net-(U$6-VCC-B)") (class "Default")
      (node (ref "F12") (pin "2") (pinfunction "2_2") (pintype "bidirectional"))
      (node (ref "U$6") (pin "P$10") (pinfunction "VCC-B_P$10") (pintype "power_in"))
    )
    (net (code "45") (name "Net-(U1-DM)") (class "Default")
      (node (ref "U$5") (pin "D-") (pinfunction "D-_D-") (pintype "bidirectional"))
      (node (ref "U1") (pin "6") (pinfunction "DM_6") (pintype "bidirectional"))
    )
    (net (code "46") (name "Net-(U1-DP)") (class "Default")
      (node (ref "U$5") (pin "D+") (pinfunction "D+_D+") (pintype "bidirectional"))
      (node (ref "U1") (pin "1") (pinfunction "DP_1") (pintype "bidirectional"))
    )
    (net (code "47") (name "Net-(U8-BST)") (class "Default")
      (node (ref "C4") (pin "1") (pinfunction "1_1") (pintype "passive"))
      (node (ref "U8") (pin "1") (pinfunction "BST_1") (pintype "bidirectional"))
    )
    (net (code "48") (name "Net-(U8-FB)") (class "Default")
      (node (ref "R8") (pin "2") (pinfunction "2_2") (pintype "passive"))
      (node (ref "R9") (pin "1") (pinfunction "1_1") (pintype "passive"))
      (node (ref "U8") (pin "3") (pinfunction "FB_3") (pintype "bidirectional"))
      (node (ref "U9") (pin "3") (pinfunction "FBO_3") (pintype "bidirectional"))
    )
    (net (code "49") (name "Net-(U8-LX)") (class "Default")
      (node (ref "C4") (pin "2") (pinfunction "2_2") (pintype "passive"))
      (node (ref "L2") (pin "1") (pinfunction "1_1") (pintype "passive"))
      (node (ref "U8") (pin "6") (pinfunction "LX_6") (pintype "bidirectional"))
    )
    (net (code "50") (name "Net-(U8-~{SHDN})") (class "Default")
      (node (ref "R7") (pin "1") (pinfunction "1_1") (pintype "passive"))
      (node (ref "U8") (pin "4") (pinfunction "~{SHDN}_4") (pintype "bidirectional"))
    )
    (net (code "51") (name "Net-(U9-VDD)") (class "Default")
      (node (ref "C3") (pin "2") (pinfunction "2_2") (pintype "passive"))
      (node (ref "R6") (pin "1") (pinfunction "1_1") (pintype "passive"))
      (node (ref "U9") (pin "5") (pinfunction "VDD_5") (pintype "bidirectional"))
    )
    (net (code "52") (name "Net-(U10-BST)") (class "Default")
      (node (ref "C12") (pin "1") (pinfunction "1_1") (pintype "passive"))
      (node (ref "U10") (pin "1") (pinfunction "BST_1") (pintype "bidirectional"))
    )
    (net (code "53") (name "Net-(U10-FB)") (class "Default")
      (node (ref "R12") (pin "2") (pinfunction "2_2") (pintype "passive"))
      (node (ref "R13") (pin "1") (pinfunction "1_1") (pintype "passive"))
      (node (ref "U10") (pin "3") (pinfunction "FB_3") (pintype "bidirectional"))
      (node (ref "U11") (pin "3") (pinfunction "FBO_3") (pintype "bidirectional"))
    )
    (net (code "54") (name "Net-(U10-LX)") (class "Default")
      (node (ref "C12") (pin "2") (pinfunction "2_2") (pintype "passive"))
      (node (ref "L1") (pin "1") (pinfunction "1_1") (pintype "passive"))
      (node (ref "U10") (pin "6") (pinfunction "LX_6") (pintype "bidirectional"))
    )
    (net (code "55") (name "Net-(U10-~{SHDN})") (class "Default")
      (node (ref "R11") (pin "1") (pinfunction "1_1") (pintype "passive"))
      (node (ref "U10") (pin "4") (pinfunction "~{SHDN}_4") (pintype "bidirectional"))
    )
    (net (code "56") (name "Net-(U11-VDD)") (class "Default")
      (node (ref "C11") (pin "2") (pinfunction "2_2") (pintype "passive"))
      (node (ref "R10") (pin "1") (pinfunction "1_1") (pintype "passive"))
      (node (ref "U11") (pin "5") (pinfunction "VDD_5") (pintype "bidirectional"))
    )
    (net (code "57") (name "Net-(U16-BST)") (class "Default")
      (node (ref "C30") (pin "1") (pinfunction "1_1") (pintype "passive"))
      (node (ref "U16") (pin "1") (pinfunction "BST_1") (pintype "bidirectional"))
    )
    (net (code "58") (name "Net-(U16-FB)") (class "Default")
      (node (ref "R24") (pin "2") (pinfunction "2_2") (pintype "passive"))
      (node (ref "R25") (pin "1") (pinfunction "1_1") (pintype "passive"))
      (node (ref "U16") (pin "3") (pinfunction "FB_3") (pintype "bidirectional"))
      (node (ref "U17") (pin "3") (pinfunction "FBO_3") (pintype "bidirectional"))
    )
    (net (code "59") (name "Net-(U16-LX)") (class "Default")
      (node (ref "C30") (pin "2") (pinfunction "2_2") (pintype "passive"))
      (node (ref "L5") (pin "1") (pinfunction "1_1") (pintype "passive"))
      (node (ref "U16") (pin "6") (pinfunction "LX_6") (pintype "bidirectional"))
    )
    (net (code "60") (name "Net-(U16-~{SHDN})") (class "Default")
      (node (ref "R23") (pin "1") (pinfunction "1_1") (pintype "passive"))
      (node (ref "U16") (pin "4") (pinfunction "~{SHDN}_4") (pintype "bidirectional"))
    )
    (net (code "61") (name "Net-(U17-VDD)") (class "Default")
      (node (ref "C29") (pin "2") (pinfunction "2_2") (pintype "passive"))
      (node (ref "R22") (pin "1") (pinfunction "1_1") (pintype "passive"))
      (node (ref "U17") (pin "5") (pinfunction "VDD_5") (pintype "bidirectional"))
    )
    (net (code "62") (name "Net-(U18-BST)") (class "Default")
      (node (ref "C36") (pin "1") (pinfunction "1_1") (pintype "passive"))
      (node (ref "U18") (pin "1") (pinfunction "BST_1") (pintype "bidirectional"))
    )
    (net (code "63") (name "Net-(U18-FB)") (class "Default")
      (node (ref "R28") (pin "2") (pinfunction "2_2") (pintype "passive"))
      (node (ref "R29") (pin "1") (pinfunction "1_1") (pintype "passive"))
      (node (ref "U18") (pin "3") (pinfunction "FB_3") (pintype "bidirectional"))
      (node (ref "U19") (pin "3") (pinfunction "FBO_3") (pintype "bidirectional"))
    )
    (net (code "64") (name "Net-(U18-LX)") (class "Default")
      (node (ref "C36") (pin "2") (pinfunction "2_2") (pintype "passive"))
      (node (ref "L6") (pin "1") (pinfunction "1_1") (pintype "passive"))
      (node (ref "U18") (pin "6") (pinfunction "LX_6") (pintype "bidirectional"))
    )
    (net (code "65") (name "Net-(U18-~{SHDN})") (class "Default")
      (node (ref "R27") (pin "1") (pinfunction "1_1") (pintype "passive"))
      (node (ref "U18") (pin "4") (pinfunction "~{SHDN}_4") (pintype "bidirectional"))
    )
    (net (code "66") (name "Net-(U19-VDD)") (class "Default")
      (node (ref "C35") (pin "2") (pinfunction "2_2") (pintype "passive"))
      (node (ref "R26") (pin "1") (pinfunction "1_1") (pintype "passive"))
      (node (ref "U19") (pin "5") (pinfunction "VDD_5") (pintype "bidirectional"))
    )
    (net (code "67") (name "PS_ON") (class "Default")
      (node (ref "SW1") (pin "2") (pinfunction "P_2") (pintype "passive"))
      (node (ref "X1") (pin "16") (pinfunction "S_16") (pintype "passive"))
    )
    (net (code "68") (name "PWR_OK") (class "Default")
      (node (ref "R2") (pin "1") (pinfunction "1_1") (pintype "passive"))
      (node (ref "X1") (pin "8") (pinfunction "S_8") (pintype "passive"))
    )
    (net (code "69") (name "unconnected-(SW1-O-Pad3)") (class "Default")
      (node (ref "SW1") (pin "3") (pinfunction "O_3") (pintype "passive"))
    )
    (net (code "70") (name "unconnected-(U1-FBO-Pad3)") (class "Default")
      (node (ref "U1") (pin "3") (pinfunction "FBO_3") (pintype "bidirectional"))
    )
    (net (code "71") (name "unconnected-(U2-FBO-Pad3)") (class "Default")
      (node (ref "U2") (pin "3") (pinfunction "FBO_3") (pintype "bidirectional"))
    )
    (net (code "72") (name "unconnected-(U3-FBO-Pad3)") (class "Default")
      (node (ref "U3") (pin "3") (pinfunction "FBO_3") (pintype "bidirectional"))
    )
    (net (code "73") (name "unconnected-(U4-FBO-Pad3)") (class "Default")
      (node (ref "U4") (pin "3") (pinfunction "FBO_3") (pintype "bidirectional"))
    )
    (net (code "74") (name "unconnected-(U5-FBO-Pad3)") (class "Default")
      (node (ref "U5") (pin "3") (pinfunction "FBO_3") (pintype "bidirectional"))
    )
    (net (code "75") (name "unconnected-(U6-FBO-Pad3)") (class "Default")
      (node (ref "U6") (pin "3") (pinfunction "FBO_3") (pintype "bidirectional"))
    )
    (net (code "76") (name "unconnected-(U7-FBO-Pad3)") (class "Default")
      (node (ref "U7") (pin "3") (pinfunction "FBO_3") (pintype "bidirectional"))
    )
    (net (code "77") (name "unconnected-(U9-QC_EN-Pad4)") (class "Default")
      (node (ref "U9") (pin "4") (pinfunction "QC_EN_4") (pintype "bidirectional"))
    )
    (net (code "78") (name "unconnected-(U11-QC_EN-Pad4)") (class "Default")
      (node (ref "U11") (pin "4") (pinfunction "QC_EN_4") (pintype "bidirectional"))
    )
    (net (code "79") (name "unconnected-(U17-QC_EN-Pad4)") (class "Default")
      (node (ref "U17") (pin "4") (pinfunction "QC_EN_4") (pintype "bidirectional"))
    )
    (net (code "80") (name "unconnected-(U19-QC_EN-Pad4)") (class "Default")
      (node (ref "U19") (pin "4") (pinfunction "QC_EN_4") (pintype "bidirectional"))
    )
  )
)
